# PIC_Schematic.net
KiCad netlist of a schematic drawn in Altium Designer
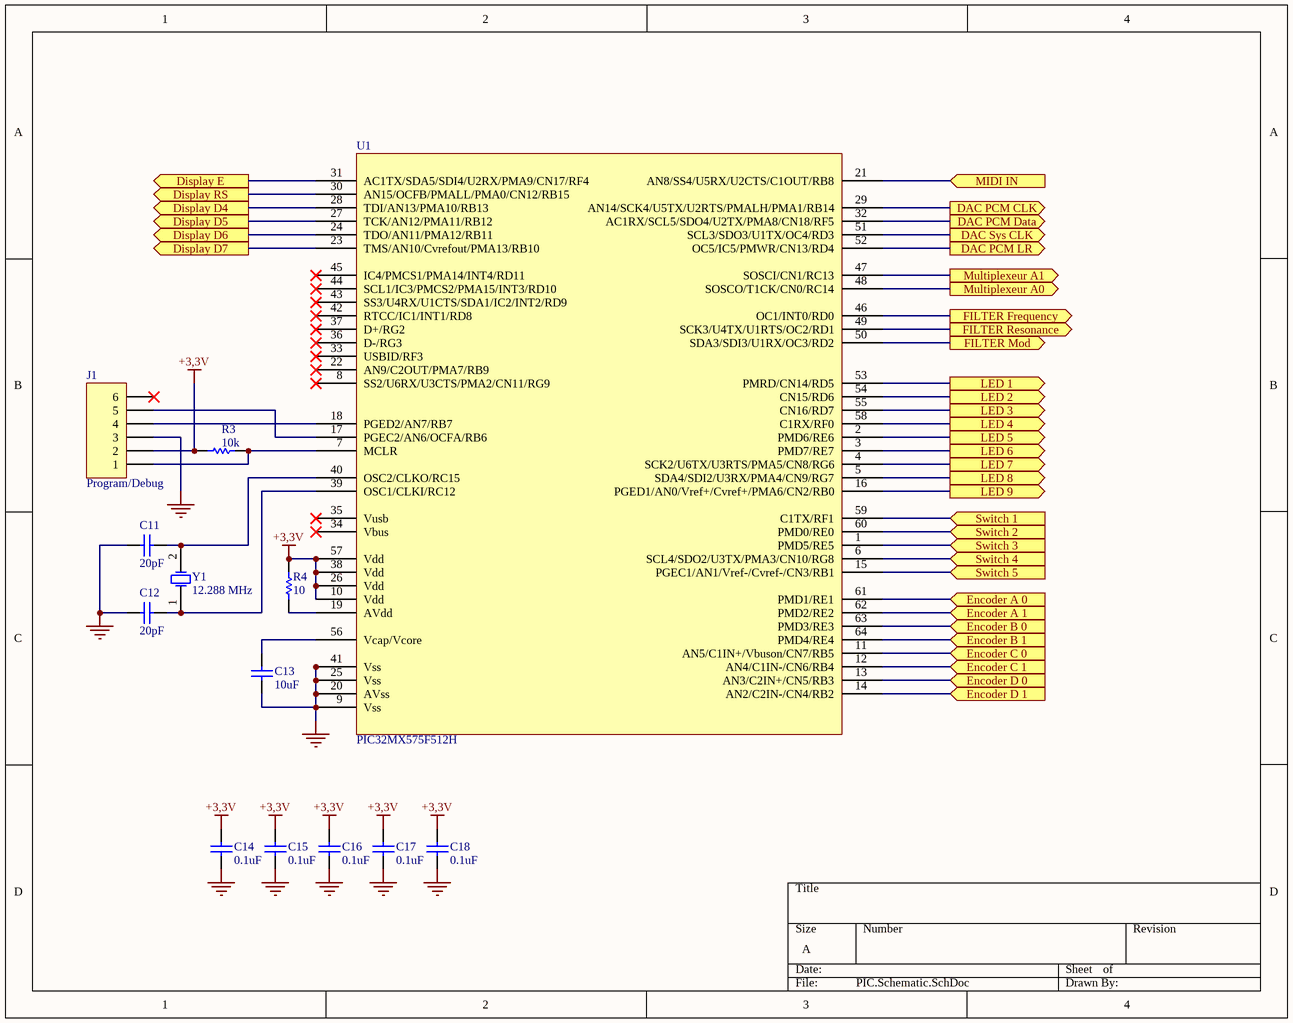
[diagram p0: PIC.Schematic.SchDoc]

(export (version "E")
  (design (tool "Eeschema 10.0.6"))
  (components
    (comp (ref "C11")
      (value "20pF")
      (footprint "CAPC1608N - cap")
      (description "Capacitor (Semiconductor SIM Model)")
      (fields (field (name "PUBLISHER") "Altium Limited"))
      (libsource (lib "Miscellaneous Devices") (part "Cap Semi"))
    )
    (comp (ref "C12")
      (value "20pF")
      (footprint "CAPC1608N - cap")
      (description "Capacitor (Semiconductor SIM Model)")
      (fields (field (name "PUBLISHER") "Altium Limited"))
      (libsource (lib "Miscellaneous Devices") (part "Cap Semi"))
    )
    (comp (ref "C13")
      (value "10uF")
      (footprint "CAPC1608N")
      (description "Capacitor")
      (fields (field (name "PUBLISHER") "Altium Limited"))
      (libsource (lib "Miscellaneous Devices") (part "Cap"))
    )
    (comp (ref "C14")
      (value "0.1uF")
      (footprint "CAPC1608N - cap")
      (description "Capacitor (Semiconductor SIM Model)")
      (fields (field (name "PUBLISHER") "Altium Limited"))
      (libsource (lib "Miscellaneous Devices") (part "Cap Semi"))
    )
    (comp (ref "C15")
      (value "0.1uF")
      (footprint "CAPC1608N - cap")
      (description "Capacitor (Semiconductor SIM Model)")
      (fields (field (name "PUBLISHER") "Altium Limited"))
      (libsource (lib "Miscellaneous Devices") (part "Cap Semi"))
    )
    (comp (ref "C16")
      (value "0.1uF")
      (footprint "CAPC1608N - cap")
      (description "Capacitor (Semiconductor SIM Model)")
      (fields (field (name "PUBLISHER") "Altium Limited"))
      (libsource (lib "Miscellaneous Devices") (part "Cap Semi"))
    )
    (comp (ref "C17")
      (value "0.1uF")
      (footprint "CAPC1608N - cap")
      (description "Capacitor (Semiconductor SIM Model)")
      (fields (field (name "PUBLISHER") "Altium Limited"))
      (libsource (lib "Miscellaneous Devices") (part "Cap Semi"))
    )
    (comp (ref "C18")
      (value "0.1uF")
      (footprint "CAPC1608N - cap")
      (description "Capacitor (Semiconductor SIM Model)")
      (fields (field (name "PUBLISHER") "Altium Limited"))
      (libsource (lib "Miscellaneous Devices") (part "Cap Semi"))
    )
    (comp (ref "J1")
      (value "Program/Debug")
      (footprint "RJ11")
      (description "Header, 6-Pin, Right Angle")
      (fields (field (name "PUBLISHER") "Altium Limited"))
      (libsource (lib "Miscellaneous Connectors") (part "Header 6H"))
    )
    (comp (ref "R3")
      (value "10k")
      (footprint "CAPC1608N")
      (description "Resistor")
      (fields (field (name "PUBLISHER") "Altium Limited"))
      (libsource (lib "Miscellaneous Devices") (part "Res1"))
    )
    (comp (ref "R4")
      (value "10")
      (footprint "CAPC1608N")
      (description "Resistor")
      (fields (field (name "PUBLISHER") "Altium Limited"))
      (libsource (lib "Miscellaneous Devices") (part "Res1"))
    )
    (comp (ref "U1")
      (value "PIC32MX575F512H")
      (footprint "PIC32")
      (libsource (lib "SynthyTwo.Components") (part "PIC32 MX575F512H"))
    )
    (comp (ref "Y1")
      (value "12.288 MHz")
      (footprint "Xtal")
      (description "Crystal Oscillator")
      (fields (field (name "PUBLISHER") "Altium Limited"))
      (libsource (lib "Miscellaneous Devices") (part "XTAL"))
    )
  )
  (nets
    (net (code "1") (name "+3,3V") (class "Default")
      (node (ref "C14") (pin "2") (pinfunction "2_2") (pintype "passive"))
      (node (ref "C15") (pin "2") (pinfunction "2_2") (pintype "passive"))
      (node (ref "C16") (pin "2") (pinfunction "2_2") (pintype "passive"))
      (node (ref "C17") (pin "2") (pinfunction "2_2") (pintype "passive"))
      (node (ref "C18") (pin "2") (pinfunction "2_2") (pintype "passive"))
      (node (ref "J1") (pin "2") (pinfunction "2_2") (pintype "passive"))
      (node (ref "R3") (pin "2") (pinfunction "2_2") (pintype "passive"))
      (node (ref "R4") (pin "1") (pinfunction "1_1") (pintype "passive"))
      (node (ref "U1") (pin "10") (pinfunction "Vdd_10") (pintype "passive"))
      (node (ref "U1") (pin "26") (pinfunction "Vdd_26") (pintype "passive"))
      (node (ref "U1") (pin "38") (pinfunction "Vdd_38") (pintype "passive"))
      (node (ref "U1") (pin "57") (pinfunction "Vdd_57") (pintype "passive"))
    )
    (net (code "2") (name "/DAC PCM CLK") (class "Default")
      (node (ref "U1") (pin "29") (pinfunction "AN14/SCK4/U5TX/U2RTS/PMALH/PMA1/RB14_29") (pintype "passive"))
    )
    (net (code "3") (name "/DAC PCM Data") (class "Default")
      (node (ref "U1") (pin "32") (pinfunction "AC1RX/SCL5/SDO4/U2TX/PMA8/CN18/RF5_32") (pintype "passive"))
    )
    (net (code "4") (name "/DAC PCM LR") (class "Default")
      (node (ref "U1") (pin "52") (pinfunction "OC5/IC5/PMWR/CN13/RD4_52") (pintype "passive"))
    )
    (net (code "5") (name "/DAC Sys CLK") (class "Default")
      (node (ref "U1") (pin "51") (pinfunction "SCL3/SDO3/U1TX/OC4/RD3_51") (pintype "passive"))
    )
    (net (code "6") (name "/Display D4") (class "Default")
      (node (ref "U1") (pin "28") (pinfunction "TDI/AN13/PMA10/RB13_28") (pintype "passive"))
    )
    (net (code "7") (name "/Display D5") (class "Default")
      (node (ref "U1") (pin "27") (pinfunction "TCK/AN12/PMA11/RB12_27") (pintype "passive"))
    )
    (net (code "8") (name "/Display D6") (class "Default")
      (node (ref "U1") (pin "24") (pinfunction "TDO/AN11/PMA12/RB11_24") (pintype "passive"))
    )
    (net (code "9") (name "/Display D7") (class "Default")
      (node (ref "U1") (pin "23") (pinfunction "TMS/AN10/Cvrefout/PMA13/RB10_23") (pintype "passive"))
    )
    (net (code "10") (name "/Display E") (class "Default")
      (node (ref "U1") (pin "31") (pinfunction "AC1TX/SDA5/SDI4/U2RX/PMA9/CN17/RF4_31") (pintype "passive"))
    )
    (net (code "11") (name "/Display RS") (class "Default")
      (node (ref "U1") (pin "30") (pinfunction "AN15/OCFB/PMALL/PMA0/CN12/RB15_30") (pintype "passive"))
    )
    (net (code "12") (name "/Encoder A 0") (class "Default")
      (node (ref "U1") (pin "61") (pinfunction "PMD1/RE1_61") (pintype "passive"))
    )
    (net (code "13") (name "/Encoder A 1") (class "Default")
      (node (ref "U1") (pin "62") (pinfunction "PMD2/RE2_62") (pintype "passive"))
    )
    (net (code "14") (name "/Encoder B 0") (class "Default")
      (node (ref "U1") (pin "63") (pinfunction "PMD3/RE3_63") (pintype "passive"))
    )
    (net (code "15") (name "/Encoder B 1") (class "Default")
      (node (ref "U1") (pin "64") (pinfunction "PMD4/RE4_64") (pintype "passive"))
    )
    (net (code "16") (name "/Encoder C 0") (class "Default")
      (node (ref "U1") (pin "11") (pinfunction "AN5/C1IN+/Vbuson/CN7/RB5_11") (pintype "passive"))
    )
    (net (code "17") (name "/Encoder C 1") (class "Default")
      (node (ref "U1") (pin "12") (pinfunction "AN4/C1IN-/CN6/RB4_12") (pintype "passive"))
    )
    (net (code "18") (name "/Encoder D 0") (class "Default")
      (node (ref "U1") (pin "13") (pinfunction "AN3/C2IN+/CN5/RB3_13") (pintype "passive"))
    )
    (net (code "19") (name "/Encoder D 1") (class "Default")
      (node (ref "U1") (pin "14") (pinfunction "AN2/C2IN-/CN4/RB2_14") (pintype "passive"))
    )
    (net (code "20") (name "/FILTER Frequency") (class "Default")
      (node (ref "U1") (pin "46") (pinfunction "OC1/INT0/RD0_46") (pintype "passive"))
    )
    (net (code "21") (name "/FILTER Mod") (class "Default")
      (node (ref "U1") (pin "50") (pinfunction "SDA3/SDI3/U1RX/OC3/RD2_50") (pintype "passive"))
    )
    (net (code "22") (name "/FILTER Resonance") (class "Default")
      (node (ref "U1") (pin "49") (pinfunction "SCK3/U4TX/U1RTS/OC2/RD1_49") (pintype "passive"))
    )
    (net (code "23") (name "/LED 1") (class "Default")
      (node (ref "U1") (pin "53") (pinfunction "PMRD/CN14/RD5_53") (pintype "passive"))
    )
    (net (code "24") (name "/LED 2") (class "Default")
      (node (ref "U1") (pin "54") (pinfunction "CN15/RD6_54") (pintype "passive"))
    )
    (net (code "25") (name "/LED 3") (class "Default")
      (node (ref "U1") (pin "55") (pinfunction "CN16/RD7_55") (pintype "passive"))
    )
    (net (code "26") (name "/LED 4") (class "Default")
      (node (ref "U1") (pin "58") (pinfunction "C1RX/RF0_58") (pintype "passive"))
    )
    (net (code "27") (name "/LED 5") (class "Default")
      (node (ref "U1") (pin "2") (pinfunction "PMD6/RE6_2") (pintype "passive"))
    )
    (net (code "28") (name "/LED 6") (class "Default")
      (node (ref "U1") (pin "3") (pinfunction "PMD7/RE7_3") (pintype "passive"))
    )
    (net (code "29") (name "/LED 7") (class "Default")
      (node (ref "U1") (pin "4") (pinfunction "SCK2/U6TX/U3RTS/PMA5/CN8/RG6_4") (pintype "passive"))
    )
    (net (code "30") (name "/LED 8") (class "Default")
      (node (ref "U1") (pin "5") (pinfunction "SDA4/SDI2/U3RX/PMA4/CN9/RG7_5") (pintype "passive"))
    )
    (net (code "31") (name "/LED 9") (class "Default")
      (node (ref "U1") (pin "16") (pinfunction "PGED1/AN0/Vref+/Cvref+/PMA6/CN2/RB0_16") (pintype "passive"))
    )
    (net (code "32") (name "/MIDI IN") (class "Default")
      (node (ref "U1") (pin "21") (pinfunction "AN8/SS4/U5RX/U2CTS/C1OUT/RB8_21") (pintype "passive"))
    )
    (net (code "33") (name "/Multiplexeur A0") (class "Default")
      (node (ref "U1") (pin "48") (pinfunction "SOSCO/T1CK/CN0/RC14_48") (pintype "passive"))
    )
    (net (code "34") (name "/Multiplexeur A1") (class "Default")
      (node (ref "U1") (pin "47") (pinfunction "SOSCI/CN1/RC13_47") (pintype "passive"))
    )
    (net (code "35") (name "/Switch 1") (class "Default")
      (node (ref "U1") (pin "59") (pinfunction "C1TX/RF1_59") (pintype "passive"))
    )
    (net (code "36") (name "/Switch 2") (class "Default")
      (node (ref "U1") (pin "60") (pinfunction "PMD0/RE0_60") (pintype "passive"))
    )
    (net (code "37") (name "/Switch 3") (class "Default")
      (node (ref "U1") (pin "1") (pinfunction "PMD5/RE5_1") (pintype "passive"))
    )
    (net (code "38") (name "/Switch 4") (class "Default")
      (node (ref "U1") (pin "6") (pinfunction "SCL4/SDO2/U3TX/PMA3/CN10/RG8_6") (pintype "passive"))
    )
    (net (code "39") (name "/Switch 5") (class "Default")
      (node (ref "U1") (pin "15") (pinfunction "PGEC1/AN1/Vref-/Cvref-/CN3/RB1_15") (pintype "passive"))
    )
    (net (code "40") (name "GND") (class "Default")
      (node (ref "C11") (pin "1") (pinfunction "1_1") (pintype "passive"))
      (node (ref "C12") (pin "1") (pinfunction "1_1") (pintype "passive"))
      (node (ref "C13") (pin "1") (pinfunction "1_1") (pintype "passive"))
      (node (ref "C14") (pin "1") (pinfunction "1_1") (pintype "passive"))
      (node (ref "C15") (pin "1") (pinfunction "1_1") (pintype "passive"))
      (node (ref "C16") (pin "1") (pinfunction "1_1") (pintype "passive"))
      (node (ref "C17") (pin "1") (pinfunction "1_1") (pintype "passive"))
      (node (ref "C18") (pin "1") (pinfunction "1_1") (pintype "passive"))
      (node (ref "J1") (pin "3") (pinfunction "3_3") (pintype "passive"))
      (node (ref "U1") (pin "20") (pinfunction "AVss_20") (pintype "passive"))
      (node (ref "U1") (pin "25") (pinfunction "Vss_25") (pintype "passive"))
      (node (ref "U1") (pin "41") (pinfunction "Vss_41") (pintype "passive"))
      (node (ref "U1") (pin "9") (pinfunction "Vss_9") (pintype "passive"))
    )
    (net (code "41") (name "Net-(U1-AVdd)") (class "Default")
      (node (ref "R4") (pin "2") (pinfunction "2_2") (pintype "passive"))
      (node (ref "U1") (pin "19") (pinfunction "AVdd_19") (pintype "passive"))
    )
    (net (code "42") (name "Net-(U1-MCLR)") (class "Default")
      (node (ref "J1") (pin "1") (pinfunction "1_1") (pintype "passive"))
      (node (ref "R3") (pin "1") (pinfunction "1_1") (pintype "passive"))
      (node (ref "U1") (pin "7") (pinfunction "MCLR_7") (pintype "passive"))
    )
    (net (code "43") (name "Net-(U1-OSC1{slash}CLKI{slash}RC12)") (class "Default")
      (node (ref "C12") (pin "2") (pinfunction "2_2") (pintype "passive"))
      (node (ref "U1") (pin "39") (pinfunction "OSC1/CLKI/RC12_39") (pintype "passive"))
      (node (ref "Y1") (pin "1") (pinfunction "OSC1_1") (pintype "passive"))
    )
    (net (code "44") (name "Net-(U1-OSC2{slash}CLKO{slash}RC15)") (class "Default")
      (node (ref "C11") (pin "2") (pinfunction "2_2") (pintype "passive"))
      (node (ref "U1") (pin "40") (pinfunction "OSC2/CLKO/RC15_40") (pintype "passive"))
      (node (ref "Y1") (pin "2") (pinfunction "OSC2_2") (pintype "passive"))
    )
    (net (code "45") (name "Net-(U1-PGEC2{slash}AN6{slash}OCFA{slash}RB6)") (class "Default")
      (node (ref "J1") (pin "5") (pinfunction "5_5") (pintype "passive"))
      (node (ref "U1") (pin "17") (pinfunction "PGEC2/AN6/OCFA/RB6_17") (pintype "passive"))
    )
    (net (code "46") (name "Net-(U1-PGED2{slash}AN7{slash}RB7)") (class "Default")
      (node (ref "J1") (pin "4") (pinfunction "4_4") (pintype "passive"))
      (node (ref "U1") (pin "18") (pinfunction "PGED2/AN7/RB7_18") (pintype "passive"))
    )
    (net (code "47") (name "Net-(U1-Vcap{slash}Vcore)") (class "Default")
      (node (ref "C13") (pin "2") (pinfunction "2_2") (pintype "passive"))
      (node (ref "U1") (pin "56") (pinfunction "Vcap/Vcore_56") (pintype "passive"))
    )
    (net (code "48") (name "unconnected-(J1-Pad6)") (class "Default")
      (node (ref "J1") (pin "6") (pinfunction "6_6") (pintype "passive+no_connect"))
    )
    (net (code "49") (name "unconnected-(U1-AN9{slash}C2OUT{slash}PMA7{slash}RB9-Pad22)") (class "Default")
      (node (ref "U1") (pin "22") (pinfunction "AN9/C2OUT/PMA7/RB9_22") (pintype "passive+no_connect"))
    )
    (net (code "50") (name "unconnected-(U1-D+{slash}RG2-Pad37)") (class "Default")
      (node (ref "U1") (pin "37") (pinfunction "D+/RG2_37") (pintype "passive+no_connect"))
    )
    (net (code "51") (name "unconnected-(U1-D-{slash}RG3-Pad36)") (class "Default")
      (node (ref "U1") (pin "36") (pinfunction "D-/RG3_36") (pintype "passive+no_connect"))
    )
    (net (code "52") (name "unconnected-(U1-IC4{slash}PMCS1{slash}PMA14{slash}INT4{slash}RD11-Pad45)") (class "Default")
      (node (ref "U1") (pin "45") (pinfunction "IC4/PMCS1/PMA14/INT4/RD11_45") (pintype "passive+no_connect"))
    )
    (net (code "53") (name "unconnected-(U1-RTCC{slash}IC1{slash}INT1{slash}RD8-Pad42)") (class "Default")
      (node (ref "U1") (pin "42") (pinfunction "RTCC/IC1/INT1/RD8_42") (pintype "passive+no_connect"))
    )
    (net (code "54") (name "unconnected-(U1-SCL1{slash}IC3{slash}PMCS2{slash}PMA15{slash}INT3{slash}RD10-Pad44)") (class "Default")
      (node (ref "U1") (pin "44") (pinfunction "SCL1/IC3/PMCS2/PMA15/INT3/RD10_44") (pintype "passive+no_connect"))
    )
    (net (code "55") (name "unconnected-(U1-SS2{slash}U6RX{slash}U3CTS{slash}PMA2{slash}CN11{slash}RG9-Pad8)") (class "Default")
      (node (ref "U1") (pin "8") (pinfunction "SS2/U6RX/U3CTS/PMA2/CN11/RG9_8") (pintype "passive+no_connect"))
    )
    (net (code "56") (name "unconnected-(U1-SS3{slash}U4RX{slash}U1CTS{slash}SDA1{slash}IC2{slash}INT2{slash}RD9-Pad43)") (class "Default")
      (node (ref "U1") (pin "43") (pinfunction "SS3/U4RX/U1CTS/SDA1/IC2/INT2/RD9_43") (pintype "passive+no_connect"))
    )
    (net (code "57") (name "unconnected-(U1-USBID{slash}RF3-Pad33)") (class "Default")
      (node (ref "U1") (pin "33") (pinfunction "USBID/RF3_33") (pintype "passive+no_connect"))
    )
    (net (code "58") (name "unconnected-(U1-Vbus-Pad34)") (class "Default")
      (node (ref "U1") (pin "34") (pinfunction "Vbus_34") (pintype "passive+no_connect"))
    )
    (net (code "59") (name "unconnected-(U1-Vusb-Pad35)") (class "Default")
      (node (ref "U1") (pin "35") (pinfunction "Vusb_35") (pintype "passive+no_connect"))
    )
  )
)
